# MapleBreakout.net
KiCad netlist of a schematic drawn in Altium Designer
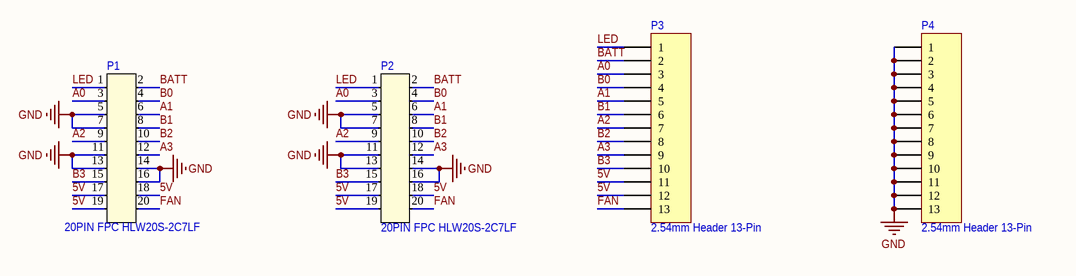
[diagram p0: MapleBreakout.SchDoc]

(export (version "E")
  (design (tool "Eeschema 10.0.6"))
  (components
    (comp (ref "P1")
      (value "20PIN FPC HLW20S-2C7LF")
      (footprint "HLW20S-2C7LF")
      (fields
        (field (name "MANUFACTURER") "Amphenol FCI")
        (field (name "MANUFACTURER PART NUMBER") "HLW20S-2C7LF")
      )
      (libsource (lib "MyLib") (part "20PIN FPC HLW20S-2C7LF"))
    )
    (comp (ref "P2")
      (value "20PIN FPC HLW20S-2C7LF")
      (footprint "HLW20S-2C7LF")
      (fields
        (field (name "MANUFACTURER") "Amphenol FCI")
        (field (name "MANUFACTURER PART NUMBER") "HLW20S-2C7LF")
      )
      (libsource (lib "MyLib") (part "20PIN FPC HLW20S-2C7LF"))
    )
    (comp (ref "P3")
      (value "2.54mm Header 13-Pin")
      (footprint "HDR1X13")
      (fields (field (name "PUBLISHER") "Altium Limited"))
      (libsource (lib "Miscellaneous Connectors") (part "Header 13"))
    )
    (comp (ref "P4")
      (value "2.54mm Header 13-Pin")
      (footprint "HDR1X13")
      (fields (field (name "PUBLISHER") "Altium Limited"))
      (libsource (lib "Miscellaneous Connectors") (part "Header 13"))
    )
  )
  (nets
    (net (code "1") (name "/5V") (class "Default")
      (node (ref "P1") (pin "17") (pintype "passive"))
      (node (ref "P1") (pin "18") (pintype "passive"))
      (node (ref "P1") (pin "19") (pintype "passive"))
      (node (ref "P2") (pin "17") (pintype "passive"))
      (node (ref "P2") (pin "18") (pintype "passive"))
      (node (ref "P2") (pin "19") (pintype "passive"))
      (node (ref "P3") (pin "11") (pinfunction "11_11") (pintype "passive"))
      (node (ref "P3") (pin "12") (pinfunction "12_12") (pintype "passive"))
    )
    (net (code "2") (name "/A0") (class "Default")
      (node (ref "P1") (pin "3") (pintype "passive"))
      (node (ref "P2") (pin "3") (pintype "passive"))
      (node (ref "P3") (pin "3") (pinfunction "3_3") (pintype "passive"))
    )
    (net (code "3") (name "/A1") (class "Default")
      (node (ref "P1") (pin "6") (pintype "passive"))
      (node (ref "P2") (pin "6") (pintype "passive"))
      (node (ref "P3") (pin "5") (pinfunction "5_5") (pintype "passive"))
    )
    (net (code "4") (name "/A2") (class "Default")
      (node (ref "P1") (pin "9") (pintype "passive"))
      (node (ref "P2") (pin "9") (pintype "passive"))
      (node (ref "P3") (pin "7") (pinfunction "7_7") (pintype "passive"))
    )
    (net (code "5") (name "/A3") (class "Default")
      (node (ref "P1") (pin "12") (pintype "passive"))
      (node (ref "P2") (pin "12") (pintype "passive"))
      (node (ref "P3") (pin "9") (pinfunction "9_9") (pintype "passive"))
    )
    (net (code "6") (name "/B0") (class "Default")
      (node (ref "P1") (pin "4") (pintype "passive"))
      (node (ref "P2") (pin "4") (pintype "passive"))
      (node (ref "P3") (pin "4") (pinfunction "4_4") (pintype "passive"))
    )
    (net (code "7") (name "/B1") (class "Default")
      (node (ref "P1") (pin "8") (pintype "passive"))
      (node (ref "P2") (pin "8") (pintype "passive"))
      (node (ref "P3") (pin "6") (pinfunction "6_6") (pintype "passive"))
    )
    (net (code "8") (name "/B2") (class "Default")
      (node (ref "P1") (pin "10") (pintype "passive"))
      (node (ref "P2") (pin "10") (pintype "passive"))
      (node (ref "P3") (pin "8") (pinfunction "8_8") (pintype "passive"))
    )
    (net (code "9") (name "/B3") (class "Default")
      (node (ref "P1") (pin "15") (pintype "passive"))
      (node (ref "P2") (pin "15") (pintype "passive"))
      (node (ref "P3") (pin "10") (pinfunction "10_10") (pintype "passive"))
    )
    (net (code "10") (name "/BATT") (class "Default")
      (node (ref "P1") (pin "2") (pintype "passive"))
      (node (ref "P2") (pin "2") (pintype "passive"))
      (node (ref "P3") (pin "2") (pinfunction "2_2") (pintype "passive"))
    )
    (net (code "11") (name "/FAN") (class "Default")
      (node (ref "P1") (pin "20") (pintype "passive"))
      (node (ref "P2") (pin "20") (pintype "passive"))
      (node (ref "P3") (pin "13") (pinfunction "13_13") (pintype "passive"))
    )
    (net (code "12") (name "/LED") (class "Default")
      (node (ref "P1") (pin "1") (pintype "passive"))
      (node (ref "P2") (pin "1") (pintype "passive"))
      (node (ref "P3") (pin "1") (pinfunction "1_1") (pintype "passive"))
    )
    (net (code "13") (name "GND") (class "Default")
      (node (ref "P1") (pin "11") (pintype "passive"))
      (node (ref "P1") (pin "13") (pintype "passive"))
      (node (ref "P1") (pin "14") (pintype "passive"))
      (node (ref "P1") (pin "16") (pintype "passive"))
      (node (ref "P1") (pin "5") (pintype "passive"))
      (node (ref "P1") (pin "7") (pintype "passive"))
      (node (ref "P2") (pin "11") (pintype "passive"))
      (node (ref "P2") (pin "13") (pintype "passive"))
      (node (ref "P2") (pin "14") (pintype "passive"))
      (node (ref "P2") (pin "16") (pintype "passive"))
      (node (ref "P2") (pin "5") (pintype "passive"))
      (node (ref "P2") (pin "7") (pintype "passive"))
      (node (ref "P4") (pin "1") (pinfunction "1_1") (pintype "passive"))
      (node (ref "P4") (pin "10") (pinfunction "10_10") (pintype "passive"))
      (node (ref "P4") (pin "11") (pinfunction "11_11") (pintype "passive"))
      (node (ref "P4") (pin "12") (pinfunction "12_12") (pintype "passive"))
      (node (ref "P4") (pin "13") (pinfunction "13_13") (pintype "passive"))
      (node (ref "P4") (pin "2") (pinfunction "2_2") (pintype "passive"))
      (node (ref "P4") (pin "3") (pinfunction "3_3") (pintype "passive"))
      (node (ref "P4") (pin "4") (pinfunction "4_4") (pintype "passive"))
      (node (ref "P4") (pin "5") (pinfunction "5_5") (pintype "passive"))
      (node (ref "P4") (pin "6") (pinfunction "6_6") (pintype "passive"))
      (node (ref "P4") (pin "7") (pinfunction "7_7") (pintype "passive"))
      (node (ref "P4") (pin "8") (pinfunction "8_8") (pintype "passive"))
      (node (ref "P4") (pin "9") (pinfunction "9_9") (pintype "passive"))
    )
  )
)
